# source_bt_rev_a.net
KiCad netlist of a schematic drawn in EAGLE
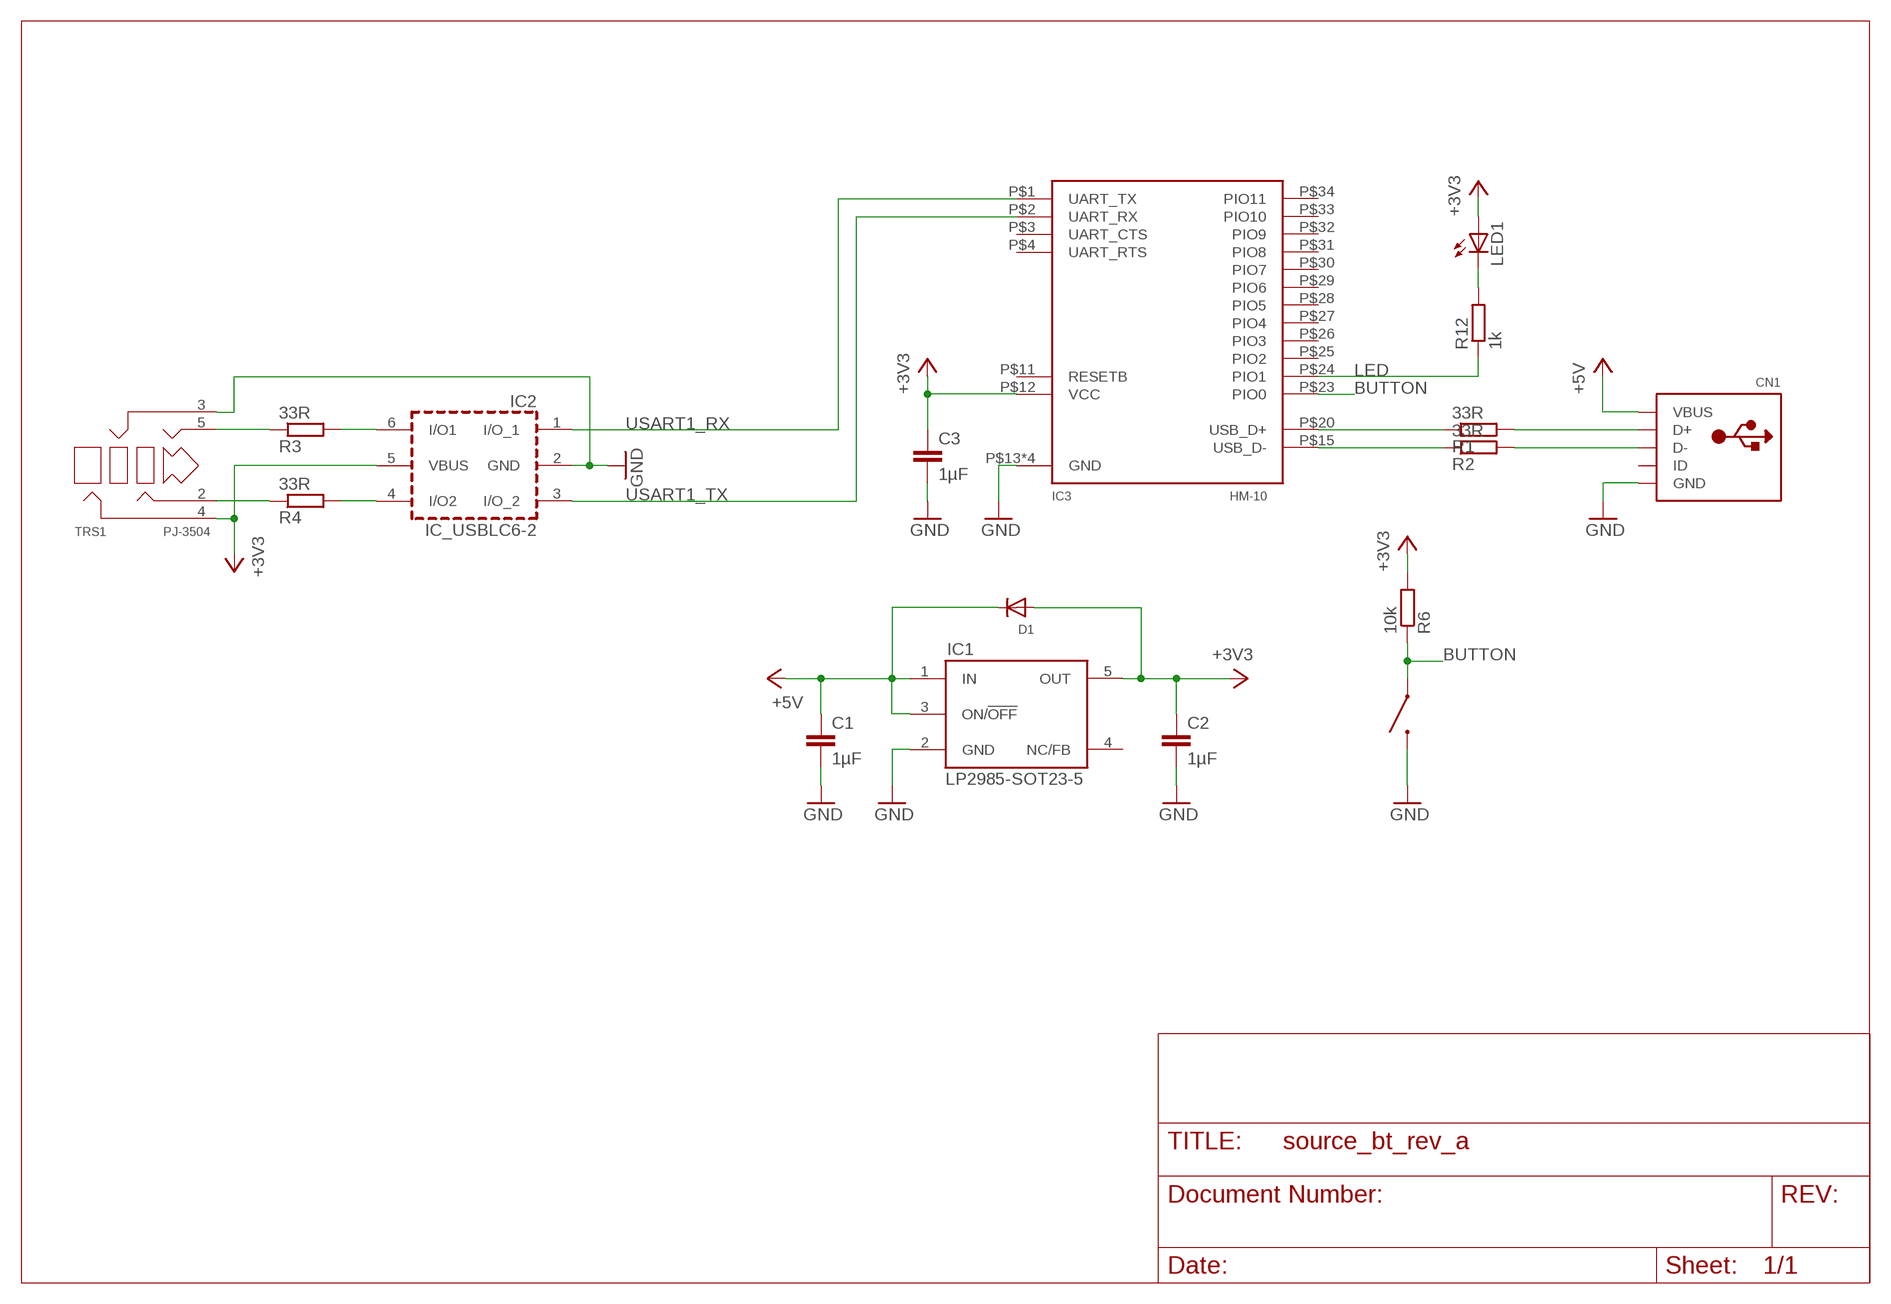
[diagram p0: schematic, sheet 1]

(export (version "E")
  (design (tool "Eeschema 10.0.6"))
  (components
    (comp (ref "C1")
      (value "1µF")
      (footprint "eagle-import:C0603")
      (libsource (lib "eagle-import") (part "C-EUC0603"))
    )
    (comp (ref "C2")
      (value "1µF")
      (footprint "eagle-import:C0603")
      (libsource (lib "eagle-import") (part "C-EUC0603"))
    )
    (comp (ref "C3")
      (value "1µF")
      (footprint "eagle-import:C0603")
      (libsource (lib "eagle-import") (part "C-EUC0603"))
    )
    (comp (ref "CN1")
      (value "USBMINIB")
      (footprint "eagle-import:USB-MINIB")
      (libsource (lib "eagle-import") (part "USBMINIB"))
    )
    (comp (ref "D1")
      (value "DIODESOD-323")
      (footprint "eagle-import:SOD-323")
      (libsource (lib "eagle-import") (part "DIODESOD-323"))
    )
    (comp (ref "IC1")
      (value "LP2985-SOT23-5")
      (footprint "eagle-import:SOT23-5")
      (libsource (lib "eagle-import") (part "LP2985-SOT23-5"))
    )
    (comp (ref "IC2")
      (value "IC_USBLC6-2")
      (footprint "eagle-import:SOT-23-6L")
      (libsource (lib "eagle-import") (part "IC_USBLC6-2"))
    )
    (comp (ref "IC3")
      (value "HM-10")
      (footprint "eagle-import:HM-10")
      (libsource (lib "eagle-import") (part "HM-10"))
    )
    (comp (ref "ISP")
      (value "TACT-SWITCH-40-40")
      (footprint "eagle-import:40-40")
      (libsource (lib "eagle-import") (part "TACT-SWITCH-40-40"))
    )
    (comp (ref "LED1")
      (value "LEDCHIP-LED0603")
      (footprint "eagle-import:CHIP-LED0603")
      (libsource (lib "eagle-import") (part "LEDCHIP-LED0603"))
    )
    (comp (ref "R1")
      (value "33R")
      (footprint "eagle-import:R0603")
      (libsource (lib "eagle-import") (part "R-EU_R0603"))
    )
    (comp (ref "R2")
      (value "33R")
      (footprint "eagle-import:R0603")
      (libsource (lib "eagle-import") (part "R-EU_R0603"))
    )
    (comp (ref "R3")
      (value "33R")
      (footprint "eagle-import:R0603")
      (libsource (lib "eagle-import") (part "R-EU_R0603"))
    )
    (comp (ref "R4")
      (value "33R")
      (footprint "eagle-import:R0603")
      (libsource (lib "eagle-import") (part "R-EU_R0603"))
    )
    (comp (ref "R6")
      (value "10k")
      (footprint "eagle-import:R0603")
      (libsource (lib "eagle-import") (part "R-EU_R0603"))
    )
    (comp (ref "R12")
      (value "1k")
      (footprint "eagle-import:R0603")
      (libsource (lib "eagle-import") (part "R-EU_R0603"))
    )
    (comp (ref "TRS1")
      (value "PJ-3504")
      (footprint "eagle-import:YD-PJ-3504")
      (libsource (lib "eagle-import") (part "PJ-3504"))
    )
  )
  (nets
    (net (code "1") (name "+3V3") (class "Default")
      (node (ref "C2") (pin "1") (pinfunction "1_1") (pintype "passive"))
      (node (ref "C3") (pin "1") (pinfunction "1_1") (pintype "passive"))
      (node (ref "D1") (pin "A") (pinfunction "A_A") (pintype "passive"))
      (node (ref "IC1") (pin "5") (pinfunction "OUT_5") (pintype "bidirectional"))
      (node (ref "IC2") (pin "5") (pinfunction "VBUS_5") (pintype "bidirectional"))
      (node (ref "IC3") (pin "P$12") (pinfunction "VCC_P$12") (pintype "bidirectional"))
      (node (ref "LED1") (pin "A") (pinfunction "A_A") (pintype "passive"))
      (node (ref "R6") (pin "2") (pinfunction "2_2") (pintype "passive"))
      (node (ref "TRS1") (pin "4") (pinfunction "4_4") (pintype "bidirectional"))
    )
    (net (code "2") (name "+5V") (class "Default")
      (node (ref "C1") (pin "1") (pinfunction "1_1") (pintype "passive"))
      (node (ref "CN1") (pin "VBUS") (pinfunction "VBUS_VBUS") (pintype "power_in"))
      (node (ref "D1") (pin "C") (pinfunction "C_C") (pintype "passive"))
      (node (ref "IC1") (pin "1") (pinfunction "IN_1") (pintype "bidirectional"))
      (node (ref "IC1") (pin "3") (pinfunction "ON/~{OFF}_3") (pintype "bidirectional"))
    )
    (net (code "3") (name "/BUTTON") (class "Default")
      (node (ref "IC3") (pin "P$23") (pinfunction "PIO0_P$23") (pintype "bidirectional"))
      (node (ref "ISP") (pin "3") (pinfunction "P$2_3") (pintype "bidirectional"))
      (node (ref "ISP") (pin "4") (pinfunction "P$2_4") (pintype "bidirectional"))
      (node (ref "R6") (pin "1") (pinfunction "1_1") (pintype "passive"))
    )
    (net (code "4") (name "/LED") (class "Default")
      (node (ref "IC3") (pin "P$24") (pinfunction "PIO1_P$24") (pintype "bidirectional"))
      (node (ref "R12") (pin "1") (pinfunction "1_1") (pintype "passive"))
    )
    (net (code "5") (name "/USART1_RX") (class "Default")
      (node (ref "IC2") (pin "1") (pinfunction "I/O_1_1") (pintype "bidirectional"))
      (node (ref "IC3") (pin "P$1") (pinfunction "UART_TX_P$1") (pintype "bidirectional"))
    )
    (net (code "6") (name "/USART1_TX") (class "Default")
      (node (ref "IC2") (pin "3") (pinfunction "I/O_2_3") (pintype "bidirectional"))
      (node (ref "IC3") (pin "P$2") (pinfunction "UART_RX_P$2") (pintype "bidirectional"))
    )
    (net (code "7") (name "GND") (class "Default")
      (node (ref "C1") (pin "2") (pinfunction "2_2") (pintype "passive"))
      (node (ref "C2") (pin "2") (pinfunction "2_2") (pintype "passive"))
      (node (ref "C3") (pin "2") (pinfunction "2_2") (pintype "passive"))
      (node (ref "CN1") (pin "GND") (pinfunction "GND_GND") (pintype "power_in"))
      (node (ref "IC1") (pin "2") (pinfunction "GND_2") (pintype "bidirectional"))
      (node (ref "IC2") (pin "2") (pinfunction "GND_2") (pintype "bidirectional"))
      (node (ref "IC3") (pin "P$13") (pinfunction "GND_P$13") (pintype "bidirectional"))
      (node (ref "IC3") (pin "P$14") (pinfunction "GND_P$14") (pintype "bidirectional"))
      (node (ref "IC3") (pin "P$21") (pinfunction "GND_P$21") (pintype "bidirectional"))
      (node (ref "IC3") (pin "P$22") (pinfunction "GND_P$22") (pintype "bidirectional"))
      (node (ref "ISP") (pin "1") (pinfunction "P$1_1") (pintype "bidirectional"))
      (node (ref "ISP") (pin "2") (pinfunction "P$1_2") (pintype "bidirectional"))
      (node (ref "TRS1") (pin "3") (pinfunction "3_3") (pintype "bidirectional"))
    )
    (net (code "8") (name "Net-(CN1-PadD+)") (class "Default")
      (node (ref "CN1") (pin "D+") (pinfunction "D+_D+") (pintype "bidirectional"))
      (node (ref "R1") (pin "2") (pinfunction "2_2") (pintype "passive"))
    )
    (net (code "9") (name "Net-(CN1-PadD-)") (class "Default")
      (node (ref "CN1") (pin "D-") (pinfunction "D-_D-") (pintype "bidirectional"))
      (node (ref "R2") (pin "2") (pinfunction "2_2") (pintype "passive"))
    )
    (net (code "10") (name "Net-(IC2-I{slash}O1)") (class "Default")
      (node (ref "IC2") (pin "6") (pinfunction "I/O1_6") (pintype "bidirectional"))
      (node (ref "R3") (pin "2") (pinfunction "2_2") (pintype "passive"))
    )
    (net (code "11") (name "Net-(IC2-I{slash}O2)") (class "Default")
      (node (ref "IC2") (pin "4") (pinfunction "I/O2_4") (pintype "bidirectional"))
      (node (ref "R4") (pin "2") (pinfunction "2_2") (pintype "passive"))
    )
    (net (code "12") (name "Net-(IC3-USB_D+)") (class "Default")
      (node (ref "IC3") (pin "P$20") (pinfunction "USB_D+_P$20") (pintype "bidirectional"))
      (node (ref "R1") (pin "1") (pinfunction "1_1") (pintype "passive"))
    )
    (net (code "13") (name "Net-(IC3-USB_D-)") (class "Default")
      (node (ref "IC3") (pin "P$15") (pinfunction "USB_D-_P$15") (pintype "bidirectional"))
      (node (ref "R2") (pin "1") (pinfunction "1_1") (pintype "passive"))
    )
    (net (code "14") (name "Net-(LED1-PadC)") (class "Default")
      (node (ref "LED1") (pin "C") (pinfunction "C_C") (pintype "passive"))
      (node (ref "R12") (pin "2") (pinfunction "2_2") (pintype "passive"))
    )
    (net (code "15") (name "Net-(R3-Pad1)") (class "Default")
      (node (ref "R3") (pin "1") (pinfunction "1_1") (pintype "passive"))
      (node (ref "TRS1") (pin "5") (pinfunction "5_5") (pintype "bidirectional"))
    )
    (net (code "16") (name "Net-(R4-Pad1)") (class "Default")
      (node (ref "R4") (pin "1") (pinfunction "1_1") (pintype "passive"))
      (node (ref "TRS1") (pin "2") (pinfunction "2_2") (pintype "bidirectional"))
    )
    (net (code "17") (name "unconnected-(CN1-PadID)") (class "Default")
      (node (ref "CN1") (pin "ID") (pinfunction "ID_ID") (pintype "bidirectional"))
    )
    (net (code "18") (name "unconnected-(IC1-NC{slash}FB-Pad4)") (class "Default")
      (node (ref "IC1") (pin "4") (pinfunction "NC/FB_4") (pintype "bidirectional"))
    )
    (net (code "19") (name "unconnected-(IC3-PIO2-PadP$25)") (class "Default")
      (node (ref "IC3") (pin "P$25") (pinfunction "PIO2_P$25") (pintype "bidirectional"))
    )
    (net (code "20") (name "unconnected-(IC3-PIO3-PadP$26)") (class "Default")
      (node (ref "IC3") (pin "P$26") (pinfunction "PIO3_P$26") (pintype "bidirectional"))
    )
    (net (code "21") (name "unconnected-(IC3-PIO4-PadP$27)") (class "Default")
      (node (ref "IC3") (pin "P$27") (pinfunction "PIO4_P$27") (pintype "bidirectional"))
    )
    (net (code "22") (name "unconnected-(IC3-PIO5-PadP$28)") (class "Default")
      (node (ref "IC3") (pin "P$28") (pinfunction "PIO5_P$28") (pintype "bidirectional"))
    )
    (net (code "23") (name "unconnected-(IC3-PIO6-PadP$29)") (class "Default")
      (node (ref "IC3") (pin "P$29") (pinfunction "PIO6_P$29") (pintype "bidirectional"))
    )
    (net (code "24") (name "unconnected-(IC3-PIO7-PadP$30)") (class "Default")
      (node (ref "IC3") (pin "P$30") (pinfunction "PIO7_P$30") (pintype "bidirectional"))
    )
    (net (code "25") (name "unconnected-(IC3-PIO8-PadP$31)") (class "Default")
      (node (ref "IC3") (pin "P$31") (pinfunction "PIO8_P$31") (pintype "bidirectional"))
    )
    (net (code "26") (name "unconnected-(IC3-PIO9-PadP$32)") (class "Default")
      (node (ref "IC3") (pin "P$32") (pinfunction "PIO9_P$32") (pintype "bidirectional"))
    )
    (net (code "27") (name "unconnected-(IC3-PIO10-PadP$33)") (class "Default")
      (node (ref "IC3") (pin "P$33") (pinfunction "PIO10_P$33") (pintype "bidirectional"))
    )
    (net (code "28") (name "unconnected-(IC3-PIO11-PadP$34)") (class "Default")
      (node (ref "IC3") (pin "P$34") (pinfunction "PIO11_P$34") (pintype "bidirectional"))
    )
    (net (code "29") (name "unconnected-(IC3-RESETB-PadP$11)") (class "Default")
      (node (ref "IC3") (pin "P$11") (pinfunction "RESETB_P$11") (pintype "bidirectional"))
    )
    (net (code "30") (name "unconnected-(IC3-UART_CTS-PadP$3)") (class "Default")
      (node (ref "IC3") (pin "P$3") (pinfunction "UART_CTS_P$3") (pintype "bidirectional"))
    )
    (net (code "31") (name "unconnected-(IC3-UART_RTS-PadP$4)") (class "Default")
      (node (ref "IC3") (pin "P$4") (pinfunction "UART_RTS_P$4") (pintype "bidirectional"))
    )
  )
)
